# Jacdac_3D_Magnetometer-RevB.net
KiCad netlist of a schematic drawn in EAGLE
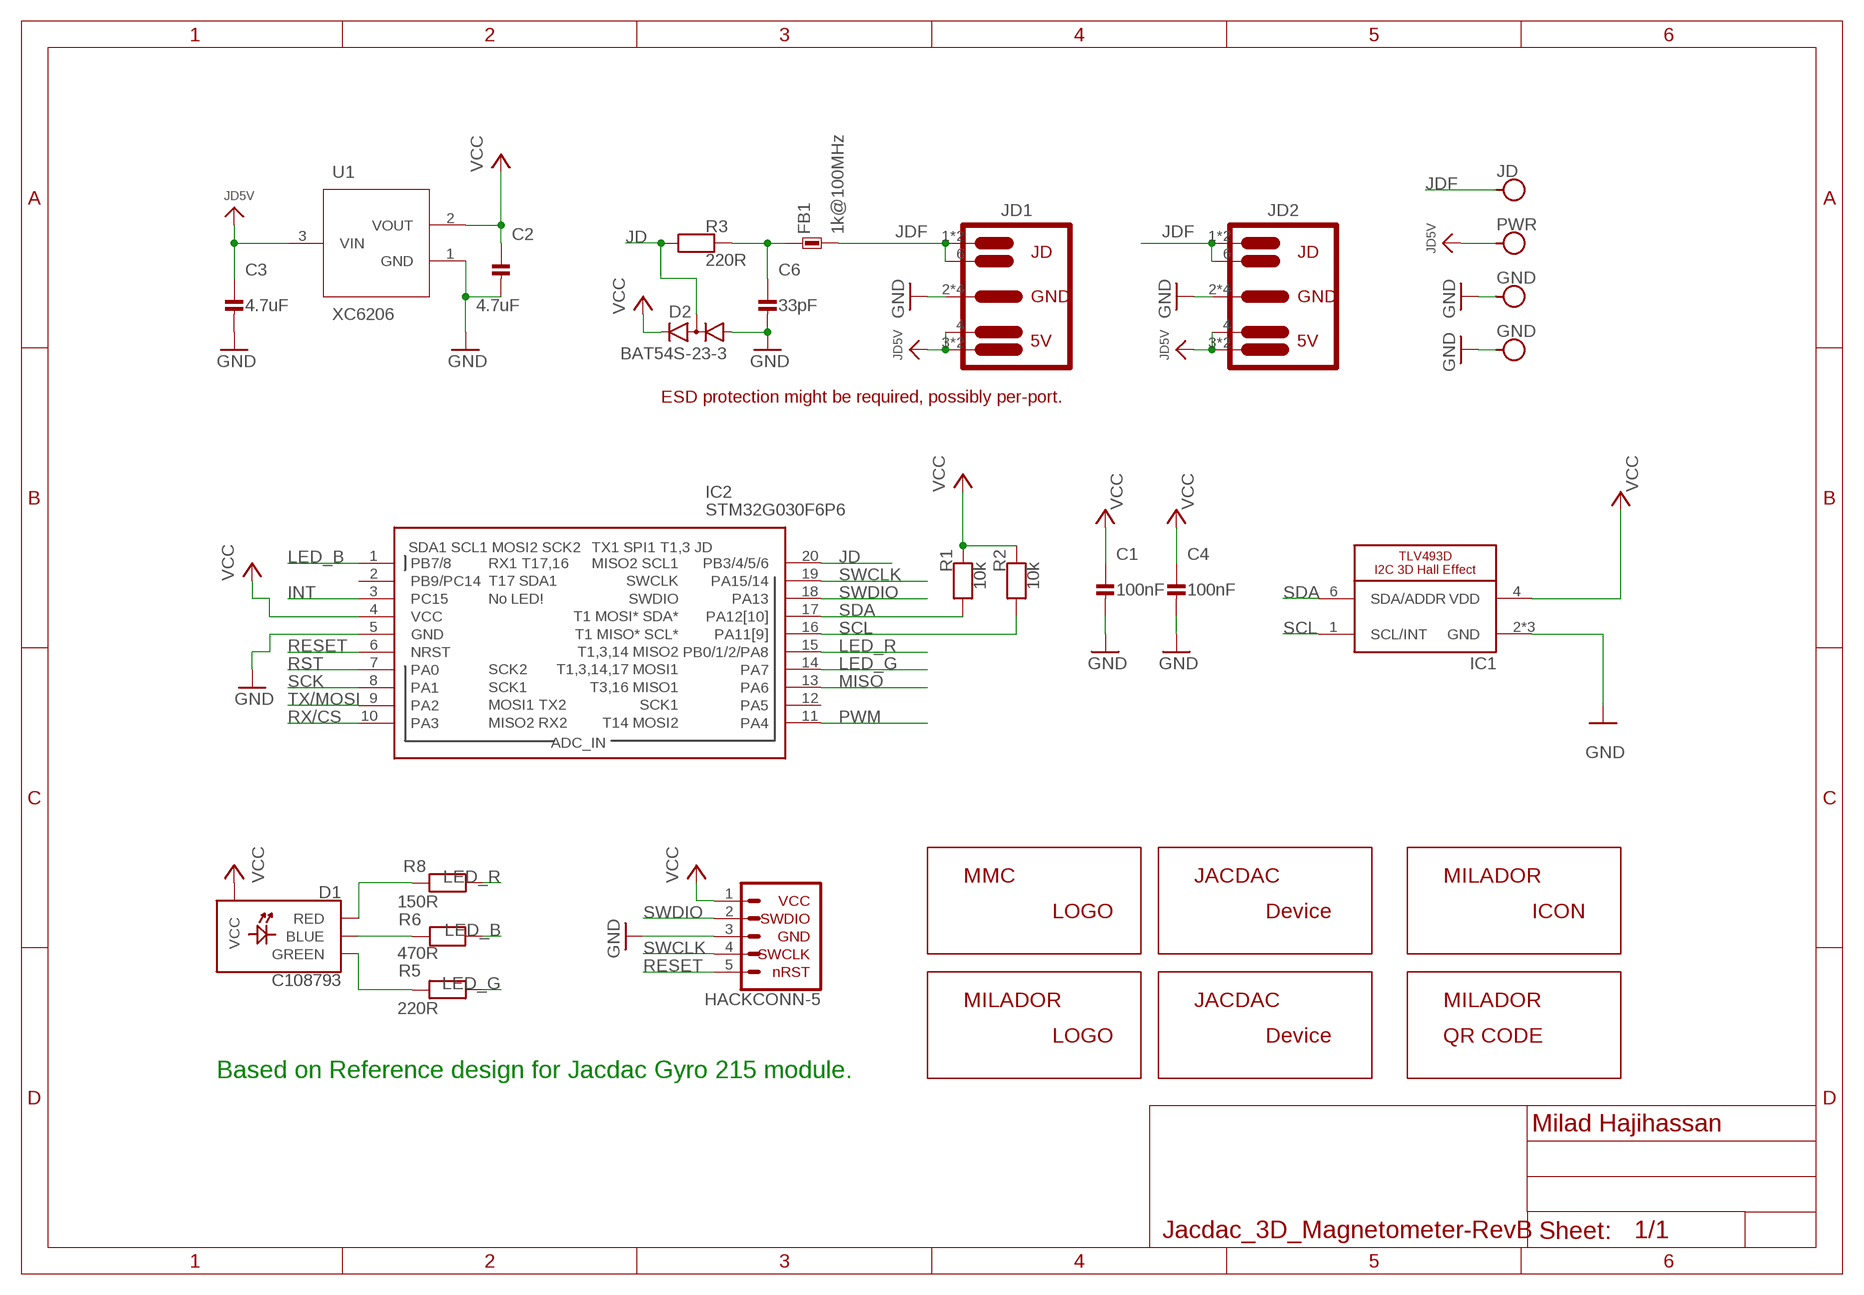
[diagram p0: schematic, sheet 1]

(export (version "E")
  (design (tool "Eeschema 10.0.6"))
  (components
    (comp (ref "C1")
      (value "100nF")
      (footprint "eagle-import:0402")
      (libsource (lib "eagle-import") (part "CAP_CERAMIC-0402"))
    )
    (comp (ref "C2")
      (value "4.7uF")
      (footprint "eagle-import:0402")
      (libsource (lib "eagle-import") (part "CAP_CERAMIC-0402"))
    )
    (comp (ref "C3")
      (value "4.7uF")
      (footprint "eagle-import:0402")
      (libsource (lib "eagle-import") (part "CAP_CERAMIC-0402"))
    )
    (comp (ref "C4")
      (value "100nF")
      (footprint "eagle-import:0402")
      (libsource (lib "eagle-import") (part "CAP_CERAMIC-0402"))
    )
    (comp (ref "C6")
      (value "33pF")
      (footprint "eagle-import:0402")
      (libsource (lib "eagle-import") (part "CAP_CERAMIC-0402"))
    )
    (comp (ref "D1")
      (value "C108793")
      (footprint "eagle-import:LED-RGB-2121")
      (libsource (lib "eagle-import") (part "LED-RGB-2121-CA"))
    )
    (comp (ref "D2")
      (value "BAT54S-23-3")
      (footprint "eagle-import:SOT23-3")
      (libsource (lib "eagle-import") (part "BAT54S-23-3"))
    )
    (comp (ref "FB1")
      (value "1k@100MHz")
      (footprint "eagle-import:0402")
      (libsource (lib "eagle-import") (part "FERRITE-BEAD-0402"))
    )
    (comp (ref "IC1")
      (value "TLV493D")
      (footprint "eagle-import:SOT23-6")
      (libsource (lib "eagle-import") (part "TLV493D"))
    )
    (comp (ref "IC2")
      (value "STM32G030F6P6")
      (footprint "eagle-import:SOP65P640X120-20N")
      (libsource (lib "eagle-import") (part "STM32G030F8P6"))
    )
    (comp (ref "J1")
      (value "JD")
      (footprint "eagle-import:M3-HOLE-DATA")
      (libsource (lib "eagle-import") (part "JACDAC-M3-DATA"))
    )
    (comp (ref "J2")
      (value "PWR")
      (footprint "eagle-import:M3-HOLE-PWR")
      (libsource (lib "eagle-import") (part "JACDAC-M3-PWR"))
    )
    (comp (ref "J3")
      (value "GND")
      (footprint "eagle-import:M3-HOLE-GND")
      (libsource (lib "eagle-import") (part "JACDAC-M3-GND"))
    )
    (comp (ref "J4")
      (value "GND")
      (footprint "eagle-import:M3-HOLE-GND")
      (libsource (lib "eagle-import") (part "JACDAC-M3-GND"))
    )
    (comp (ref "J5")
      (value "HACK-CONNECT-5")
      (footprint "eagle-import:HC5-22-62")
      (libsource (lib "eagle-import") (part "HACK-CONNECT-5"))
    )
    (comp (ref "JD1")
      (value "JACDAC-EDGE-OUTIE")
      (footprint "eagle-import:JD-EDGE-OUTIE")
      (libsource (lib "eagle-import") (part "JACDAC-EDGE-OUTIE"))
    )
    (comp (ref "JD2")
      (value "JACDAC-EDGE-OUTIE")
      (footprint "eagle-import:JD-EDGE-OUTIE")
      (libsource (lib "eagle-import") (part "JACDAC-EDGE-OUTIE"))
    )
    (comp (ref "LABEL_DEVICE")
      (value "MILADOR-JACDAC-DEVICE-MAGNETOMETER")
      (footprint "eagle-import:JACDAC-3D-MAGNETOMETER")
      (libsource (lib "eagle-import") (part "MILADOR-JACDAC-DEVICE-MAGNETOMETER"))
    )
    (comp (ref "LABEL_ICON")
      (value "MILADOR-ICON-MAG")
      (footprint "eagle-import:MILADOR_ICON_MAGNETOMETER")
      (libsource (lib "eagle-import") (part "MILADOR-ICON-MAG"))
    )
    (comp (ref "LABEL_LOGO1")
      (value "MILADOR-LOGO-SM")
      (footprint "eagle-import:MILADOR_LOGO2")
      (libsource (lib "eagle-import") (part "MILADOR-LOGO-SM"))
    )
    (comp (ref "LABEL_LOGO2")
      (value "MMC_LOGO-XSM")
      (footprint "eagle-import:MMC_X-SMALL_LOGO")
      (libsource (lib "eagle-import") (part "MMC_LOGO-XSM"))
    )
    (comp (ref "LABEL_QRCODE")
      (value "MILADOR-QR-CODE-JACDAC-MAGNETOMETER")
      (footprint "eagle-import:MILADOR_QR_JACDAC_MAGNETOMETER")
      (libsource (lib "eagle-import") (part "MILADOR-QR-CODE-JACDAC-MAGNETOMETER"))
    )
    (comp (ref "LABEL_TLV493D")
      (value "MILADOR-JACDAC-DEVICE-TLV493D")
      (footprint "eagle-import:JACDAC-TLV493D")
      (libsource (lib "eagle-import") (part "MILADOR-JACDAC-DEVICE-TLV493D"))
    )
    (comp (ref "R1")
      (value "10k")
      (footprint "eagle-import:0402")
      (libsource (lib "eagle-import") (part "RESISTOR-0402"))
    )
    (comp (ref "R2")
      (value "10k")
      (footprint "eagle-import:0402")
      (libsource (lib "eagle-import") (part "RESISTOR-0402"))
    )
    (comp (ref "R3")
      (value "220R")
      (footprint "eagle-import:0402")
      (libsource (lib "eagle-import") (part "RESISTOR-0402"))
    )
    (comp (ref "R5")
      (value "220R")
      (footprint "eagle-import:0402")
      (libsource (lib "eagle-import") (part "RESISTOR-0402"))
    )
    (comp (ref "R6")
      (value "470R")
      (footprint "eagle-import:0402")
      (libsource (lib "eagle-import") (part "RESISTOR-0402"))
    )
    (comp (ref "R8")
      (value "150R")
      (footprint "eagle-import:0402")
      (libsource (lib "eagle-import") (part "RESISTOR-0402"))
    )
    (comp (ref "U1")
      (value "XC6206")
      (footprint "eagle-import:SOT23-3-W")
      (libsource (lib "eagle-import") (part "XC6206"))
    )
  )
  (nets
    (net (code "1") (name "/INT") (class "Default")
      (node (ref "IC2") (pin "3") (pinfunction "PC15_3") (pintype "bidirectional"))
    )
    (net (code "2") (name "/JD") (class "Default")
      (node (ref "D2") (pin "3") (pinfunction "C1A2_3") (pintype "passive"))
      (node (ref "IC2") (pin "20") (pinfunction "PB3/4/5/6_20") (pintype "bidirectional"))
      (node (ref "R3") (pin "1") (pinfunction "1_1") (pintype "passive"))
    )
    (net (code "3") (name "/JDF") (class "Default")
      (node (ref "FB1") (pin "2") (pinfunction "2_2") (pintype "passive"))
      (node (ref "J1") (pin "H") (pinfunction "P$1_H") (pintype "bidirectional"))
      (node (ref "JD1") (pin "1") (pinfunction "2_1") (pintype "bidirectional"))
      (node (ref "JD1") (pin "6") (pinfunction "6_6") (pintype "bidirectional"))
      (node (ref "JD1") (pin "P$3") (pinfunction "2_P$3") (pintype "bidirectional"))
      (node (ref "JD2") (pin "1") (pinfunction "2_1") (pintype "bidirectional"))
      (node (ref "JD2") (pin "6") (pinfunction "6_6") (pintype "bidirectional"))
      (node (ref "JD2") (pin "P$3") (pinfunction "2_P$3") (pintype "bidirectional"))
    )
    (net (code "4") (name "/LED_B") (class "Default")
      (node (ref "IC2") (pin "1") (pinfunction "PB7/8_1") (pintype "input"))
      (node (ref "R6") (pin "1") (pinfunction "1_1") (pintype "passive"))
    )
    (net (code "5") (name "/LED_G") (class "Default")
      (node (ref "IC2") (pin "14") (pinfunction "PA7_14") (pintype "bidirectional"))
      (node (ref "R5") (pin "1") (pinfunction "1_1") (pintype "passive"))
    )
    (net (code "6") (name "/LED_R") (class "Default")
      (node (ref "IC2") (pin "15") (pinfunction "PB0/1/2/PA8_15") (pintype "input"))
      (node (ref "R8") (pin "1") (pinfunction "1_1") (pintype "passive"))
    )
    (net (code "7") (name "/MISO") (class "Default")
      (node (ref "IC2") (pin "13") (pinfunction "PA6_13") (pintype "bidirectional"))
    )
    (net (code "8") (name "/PWM") (class "Default")
      (node (ref "IC2") (pin "11") (pinfunction "PA4_11") (pintype "bidirectional"))
    )
    (net (code "9") (name "/RESET") (class "Default")
      (node (ref "IC2") (pin "6") (pinfunction "NRST_6") (pintype "bidirectional"))
      (node (ref "J5") (pin "5") (pinfunction "NRST_5") (pintype "bidirectional"))
    )
    (net (code "10") (name "/RST") (class "Default")
      (node (ref "IC2") (pin "7") (pinfunction "PA0_7") (pintype "bidirectional"))
    )
    (net (code "11") (name "/RX{slash}CS") (class "Default")
      (node (ref "IC2") (pin "10") (pinfunction "PA3_10") (pintype "bidirectional"))
    )
    (net (code "12") (name "/SCK") (class "Default")
      (node (ref "IC2") (pin "8") (pinfunction "PA1_8") (pintype "bidirectional"))
    )
    (net (code "13") (name "/SCL") (class "Default")
      (node (ref "IC1") (pin "1") (pinfunction "SCL/INT_1") (pintype "bidirectional"))
      (node (ref "IC2") (pin "16") (pinfunction "PA11[9]_16") (pintype "bidirectional"))
      (node (ref "R2") (pin "1") (pinfunction "1_1") (pintype "passive"))
    )
    (net (code "14") (name "/SDA") (class "Default")
      (node (ref "IC1") (pin "6") (pinfunction "SDA/ADDR_6") (pintype "bidirectional"))
      (node (ref "IC2") (pin "17") (pinfunction "PA12[10]_17") (pintype "bidirectional"))
      (node (ref "R1") (pin "1") (pinfunction "1_1") (pintype "passive"))
    )
    (net (code "15") (name "/SWCLK") (class "Default")
      (node (ref "IC2") (pin "19") (pinfunction "PA15/14_19") (pintype "bidirectional"))
      (node (ref "J5") (pin "4") (pinfunction "SWCLK_4") (pintype "input"))
    )
    (net (code "16") (name "/SWDIO") (class "Default")
      (node (ref "IC2") (pin "18") (pinfunction "PA13_18") (pintype "bidirectional"))
      (node (ref "J5") (pin "2") (pinfunction "SWDIO_2") (pintype "input"))
    )
    (net (code "17") (name "/TX{slash}MOSI") (class "Default")
      (node (ref "IC2") (pin "9") (pinfunction "PA2_9") (pintype "bidirectional"))
    )
    (net (code "18") (name "GND") (class "Default")
      (node (ref "C1") (pin "2") (pinfunction "2_2") (pintype "passive"))
      (node (ref "C2") (pin "2") (pinfunction "2_2") (pintype "passive"))
      (node (ref "C3") (pin "2") (pinfunction "2_2") (pintype "passive"))
      (node (ref "C4") (pin "2") (pinfunction "2_2") (pintype "passive"))
      (node (ref "C6") (pin "2") (pinfunction "2_2") (pintype "passive"))
      (node (ref "D2") (pin "1") (pinfunction "A1_1") (pintype "passive"))
      (node (ref "IC1") (pin "2") (pinfunction "GND_2") (pintype "power_in"))
      (node (ref "IC1") (pin "3") (pinfunction "GND_3") (pintype "power_in"))
      (node (ref "IC1") (pin "5") (pinfunction "GND_5") (pintype "power_in"))
      (node (ref "IC2") (pin "5") (pinfunction "GND_5") (pintype "power_in"))
      (node (ref "J3") (pin "H") (pinfunction "P$1_H") (pintype "bidirectional"))
      (node (ref "J4") (pin "H") (pinfunction "P$1_H") (pintype "bidirectional"))
      (node (ref "J5") (pin "3") (pinfunction "GND_3") (pintype "power_in"))
      (node (ref "JD1") (pin "2") (pinfunction "1_2") (pintype "power_in"))
      (node (ref "JD1") (pin "5") (pinfunction "1_5") (pintype "power_in"))
      (node (ref "JD1") (pin "P$2") (pinfunction "1_P$2") (pintype "power_in"))
      (node (ref "JD1") (pin "P$4") (pinfunction "1_P$4") (pintype "power_in"))
      (node (ref "JD2") (pin "2") (pinfunction "1_2") (pintype "power_in"))
      (node (ref "JD2") (pin "5") (pinfunction "1_5") (pintype "power_in"))
      (node (ref "JD2") (pin "P$2") (pinfunction "1_P$2") (pintype "power_in"))
      (node (ref "JD2") (pin "P$4") (pinfunction "1_P$4") (pintype "power_in"))
      (node (ref "U1") (pin "1") (pinfunction "GND_1") (pintype "passive"))
    )
    (net (code "19") (name "JD5V") (class "Default")
      (node (ref "C3") (pin "1") (pinfunction "1_1") (pintype "passive"))
      (node (ref "J2") (pin "H") (pinfunction "P$1_H") (pintype "bidirectional"))
      (node (ref "JD1") (pin "3") (pinfunction "3_3") (pintype "power_in"))
      (node (ref "JD1") (pin "4") (pinfunction "4_4") (pintype "power_in"))
      (node (ref "JD1") (pin "P$1") (pinfunction "3_P$1") (pintype "power_in"))
      (node (ref "JD2") (pin "3") (pinfunction "3_3") (pintype "power_in"))
      (node (ref "JD2") (pin "4") (pinfunction "4_4") (pintype "power_in"))
      (node (ref "JD2") (pin "P$1") (pinfunction "3_P$1") (pintype "power_in"))
      (node (ref "U1") (pin "3") (pinfunction "VIN_3") (pintype "input"))
    )
    (net (code "20") (name "Net-(C6-Pad1)") (class "Default")
      (node (ref "C6") (pin "1") (pinfunction "1_1") (pintype "passive"))
      (node (ref "FB1") (pin "1") (pinfunction "1_1") (pintype "passive"))
      (node (ref "R3") (pin "2") (pinfunction "2_2") (pintype "passive"))
    )
    (net (code "21") (name "Net-(D1-BLUE)") (class "Default")
      (node (ref "D1") (pin "B-") (pinfunction "BLUE_B-") (pintype "bidirectional"))
      (node (ref "R6") (pin "2") (pinfunction "2_2") (pintype "passive"))
    )
    (net (code "22") (name "Net-(D1-GREEN)") (class "Default")
      (node (ref "D1") (pin "G-") (pinfunction "GREEN_G-") (pintype "bidirectional"))
      (node (ref "R5") (pin "2") (pinfunction "2_2") (pintype "passive"))
    )
    (net (code "23") (name "Net-(D1-RED)") (class "Default")
      (node (ref "D1") (pin "R-") (pinfunction "RED_R-") (pintype "bidirectional"))
      (node (ref "R8") (pin "2") (pinfunction "2_2") (pintype "passive"))
    )
    (net (code "24") (name "VCC") (class "Default")
      (node (ref "C1") (pin "1") (pinfunction "1_1") (pintype "passive"))
      (node (ref "C2") (pin "1") (pinfunction "1_1") (pintype "passive"))
      (node (ref "C4") (pin "1") (pinfunction "1_1") (pintype "passive"))
      (node (ref "D1") (pin "PLUS") (pinfunction "VCC_PLUS") (pintype "bidirectional"))
      (node (ref "D2") (pin "2") (pinfunction "C2_2") (pintype "passive"))
      (node (ref "IC1") (pin "4") (pinfunction "VDD_4") (pintype "power_in"))
      (node (ref "IC2") (pin "4") (pinfunction "VCC_4") (pintype "power_in"))
      (node (ref "J5") (pin "1") (pinfunction "VCC_1") (pintype "passive"))
      (node (ref "R1") (pin "2") (pinfunction "2_2") (pintype "passive"))
      (node (ref "R2") (pin "2") (pinfunction "2_2") (pintype "passive"))
      (node (ref "U1") (pin "2") (pinfunction "VOUT_2") (pintype "power_in"))
    )
    (net (code "25") (name "unconnected-(IC2-PA5-Pad12)") (class "Default")
      (node (ref "IC2") (pin "12") (pinfunction "PA5_12") (pintype "bidirectional"))
    )
    (net (code "26") (name "unconnected-(IC2-PB9{slash}PC14-Pad2)") (class "Default")
      (node (ref "IC2") (pin "2") (pinfunction "PB9/PC14_2") (pintype "bidirectional"))
    )
  )
)
